# DRIVER_A.net
KiCad netlist of a schematic drawn in Altium Designer
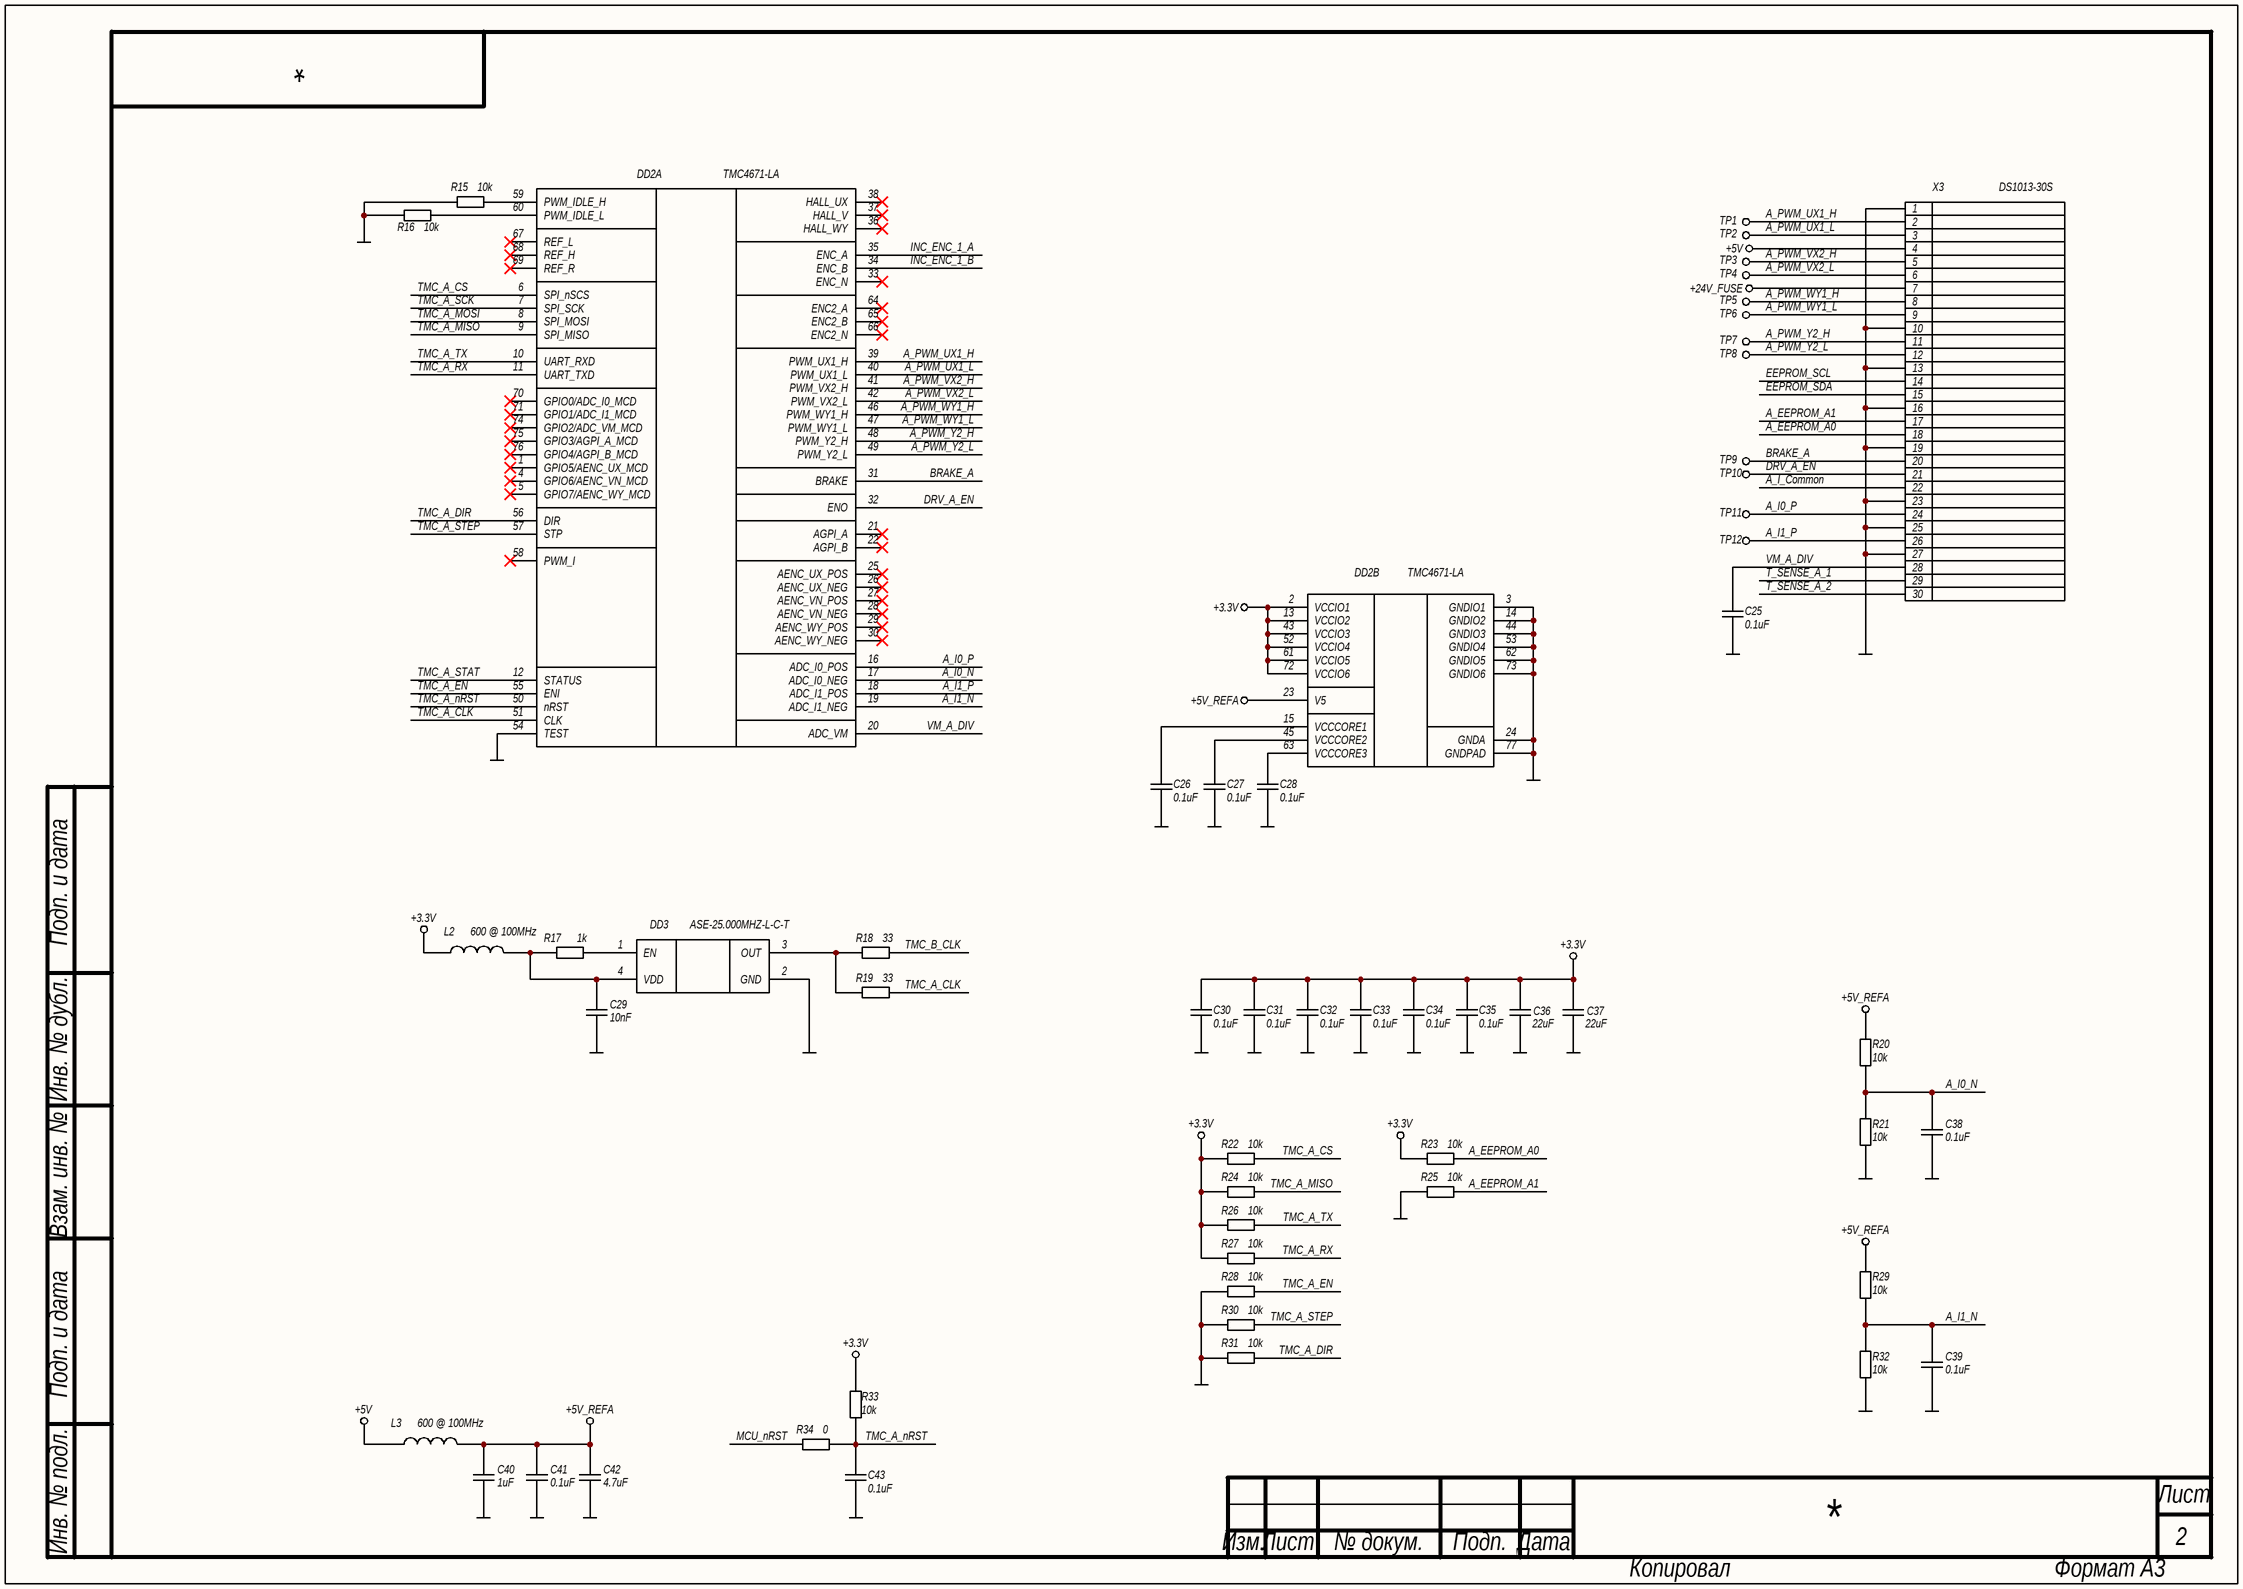
[diagram p0: DRIVER_A.SchDoc]

(export (version "E")
  (design (tool "Eeschema 10.0.6"))
  (components
    (comp (ref "C25")
      (value "0.1uF")
      (footprint "C0603N")
      (description "Конденсатор")
      (libsource (lib "Components Library") (part "CAP_FIXED"))
    )
    (comp (ref "C26")
      (value "0.1uF")
      (footprint "C0603N")
      (description "Конденсатор")
      (libsource (lib "Components Library") (part "CAP_FIXED"))
    )
    (comp (ref "C27")
      (value "0.1uF")
      (footprint "C0603N")
      (description "Конденсатор")
      (libsource (lib "Components Library") (part "CAP_FIXED"))
    )
    (comp (ref "C28")
      (value "0.1uF")
      (footprint "C0603N")
      (description "Конденсатор")
      (libsource (lib "Components Library") (part "CAP_FIXED"))
    )
    (comp (ref "C29")
      (value "10nF")
      (footprint "C0603N")
      (description "Конденсатор")
      (libsource (lib "Components Library") (part "CAP_FIXED"))
    )
    (comp (ref "C30")
      (value "0.1uF")
      (footprint "C0603N")
      (description "Конденсатор")
      (libsource (lib "Components Library") (part "CAP_FIXED"))
    )
    (comp (ref "C31")
      (value "0.1uF")
      (footprint "C0603N")
      (description "Конденсатор")
      (libsource (lib "Components Library") (part "CAP_FIXED"))
    )
    (comp (ref "C32")
      (value "0.1uF")
      (footprint "C0603N")
      (description "Конденсатор")
      (libsource (lib "Components Library") (part "CAP_FIXED"))
    )
    (comp (ref "C33")
      (value "0.1uF")
      (footprint "C0603N")
      (description "Конденсатор")
      (libsource (lib "Components Library") (part "CAP_FIXED"))
    )
    (comp (ref "C34")
      (value "0.1uF")
      (footprint "C0603N")
      (description "Конденсатор")
      (libsource (lib "Components Library") (part "CAP_FIXED"))
    )
    (comp (ref "C35")
      (value "0.1uF")
      (footprint "C0603N")
      (description "Конденсатор")
      (libsource (lib "Components Library") (part "CAP_FIXED"))
    )
    (comp (ref "C36")
      (value "22uF")
      (footprint "C0805N")
      (description "Конденсатор")
      (libsource (lib "Components Library") (part "CAP_FIXED"))
    )
    (comp (ref "C37")
      (value "22uF")
      (footprint "C0805N")
      (description "Конденсатор")
      (libsource (lib "Components Library") (part "CAP_FIXED"))
    )
    (comp (ref "C38")
      (value "0.1uF")
      (footprint "C0603N")
      (description "Конденсатор")
      (libsource (lib "Components Library") (part "CAP_FIXED"))
    )
    (comp (ref "C39")
      (value "0.1uF")
      (footprint "C0603N")
      (description "Конденсатор")
      (libsource (lib "Components Library") (part "CAP_FIXED"))
    )
    (comp (ref "C40")
      (value "1uF")
      (footprint "C0603N")
      (description "Конденсатор")
      (libsource (lib "Components Library") (part "CAP_FIXED"))
    )
    (comp (ref "C41")
      (value "0.1uF")
      (footprint "C0603N")
      (description "Конденсатор")
      (libsource (lib "Components Library") (part "CAP_FIXED"))
    )
    (comp (ref "C42")
      (value "4.7uF")
      (footprint "C0603N")
      (description "Конденсатор")
      (libsource (lib "Components Library") (part "CAP_FIXED"))
    )
    (comp (ref "C43")
      (value "0.1uF")
      (footprint "C0603N")
      (description "Конденсатор")
      (libsource (lib "Components Library") (part "CAP_FIXED"))
    )
    (comp (ref "DD2")
      (value "TMC4671-LA")
      (footprint "QFN76-EP")
      (description "Микросхема драйвер двигателя")
      (libsource (lib "Components Library") (part "TMC4671-LA"))
    )
    (comp (ref "DD3")
      (value "ASE-25.000MHZ-L-C-T")
      (footprint "ASE")
      (description "Кварцевый генератор")
      (libsource (lib "Components Library") (part "XTAL_OSC"))
    )
    (comp (ref "L2")
      (value "600 @ 100MHz")
      (footprint "FB0603N")
      (description "Фильтр ЭМП индуктивный")
      (libsource (lib "") (part "IND_FILTER_1"))
    )
    (comp (ref "L3")
      (value "600 @ 100MHz")
      (footprint "FB0603N")
      (description "Фильтр ЭМП индуктивный")
      (libsource (lib "Components Library") (part "IND_FILTER"))
    )
    (comp (ref "R15")
      (value "10k")
      (footprint "R0603N")
      (description "Резистор")
      (libsource (lib "") (part "RES_FIXED_1"))
    )
    (comp (ref "R16")
      (value "10k")
      (footprint "R0603N")
      (description "Резистор")
      (libsource (lib "") (part "RES_FIXED_1"))
    )
    (comp (ref "R17")
      (value "1k")
      (footprint "R0603N")
      (description "Резистор")
      (libsource (lib "") (part "RES_FIXED_2"))
    )
    (comp (ref "R18")
      (value "33")
      (footprint "R0603N")
      (description "Резистор")
      (libsource (lib "") (part "RES_FIXED_1"))
    )
    (comp (ref "R19")
      (value "33")
      (footprint "R0603N")
      (description "Резистор")
      (libsource (lib "") (part "RES_FIXED_1"))
    )
    (comp (ref "R20")
      (value "10k")
      (footprint "R0603N")
      (description "Резистор")
      (libsource (lib "Components Library") (part "RES_FIXED"))
    )
    (comp (ref "R21")
      (value "10k")
      (footprint "R0603N")
      (description "Резистор")
      (libsource (lib "Components Library") (part "RES_FIXED"))
    )
    (comp (ref "R22")
      (value "10k")
      (footprint "R0603N")
      (description "Резистор")
      (libsource (lib "") (part "RES_FIXED_1"))
    )
    (comp (ref "R23")
      (value "10k")
      (footprint "R0603N")
      (description "Резистор")
      (libsource (lib "") (part "RES_FIXED_1"))
    )
    (comp (ref "R24")
      (value "10k")
      (footprint "R0603N")
      (description "Резистор")
      (libsource (lib "") (part "RES_FIXED_1"))
    )
    (comp (ref "R25")
      (value "10k")
      (footprint "R0603N")
      (description "Резистор")
      (libsource (lib "") (part "RES_FIXED_1"))
    )
    (comp (ref "R26")
      (value "10k")
      (footprint "R0603N")
      (description "Резистор")
      (libsource (lib "") (part "RES_FIXED_1"))
    )
    (comp (ref "R27")
      (value "10k")
      (footprint "R0603N")
      (description "Резистор")
      (libsource (lib "") (part "RES_FIXED_1"))
    )
    (comp (ref "R28")
      (value "10k")
      (footprint "R0603N")
      (description "Резистор")
      (libsource (lib "") (part "RES_FIXED_1"))
    )
    (comp (ref "R29")
      (value "10k")
      (footprint "R0603N")
      (description "Резистор")
      (libsource (lib "Components Library") (part "RES_FIXED"))
    )
    (comp (ref "R30")
      (value "10k")
      (footprint "R0603N")
      (description "Резистор")
      (libsource (lib "") (part "RES_FIXED_1"))
    )
    (comp (ref "R31")
      (value "10k")
      (footprint "R0603N")
      (description "Резистор")
      (libsource (lib "") (part "RES_FIXED_1"))
    )
    (comp (ref "R32")
      (value "10k")
      (footprint "R0603N")
      (description "Резистор")
      (libsource (lib "Components Library") (part "RES_FIXED"))
    )
    (comp (ref "R33")
      (value "10k")
      (footprint "R0603N")
      (description "Резистор")
      (libsource (lib "Components Library") (part "RES_FIXED"))
    )
    (comp (ref "R34")
      (value "0")
      (footprint "R0603N")
      (description "Резистор")
      (libsource (lib "") (part "RES_FIXED_1"))
    )
    (comp (ref "TP1")
      (value "TEST_POINT")
      (footprint "TP_RPAD_0.8MM")
      (description "Контрольная точка")
      (libsource (lib "Components Library") (part "TEST_POINT"))
    )
    (comp (ref "TP2")
      (value "TEST_POINT")
      (footprint "TP_RPAD_0.8MM")
      (description "Контрольная точка")
      (libsource (lib "Components Library") (part "TEST_POINT"))
    )
    (comp (ref "TP3")
      (value "TEST_POINT")
      (footprint "TP_RPAD_0.8MM")
      (description "Контрольная точка")
      (libsource (lib "Components Library") (part "TEST_POINT"))
    )
    (comp (ref "TP4")
      (value "TEST_POINT")
      (footprint "TP_RPAD_0.8MM")
      (description "Контрольная точка")
      (libsource (lib "Components Library") (part "TEST_POINT"))
    )
    (comp (ref "TP5")
      (value "TEST_POINT")
      (footprint "TP_RPAD_0.8MM")
      (description "Контрольная точка")
      (libsource (lib "Components Library") (part "TEST_POINT"))
    )
    (comp (ref "TP6")
      (value "TEST_POINT")
      (footprint "TP_RPAD_0.8MM")
      (description "Контрольная точка")
      (libsource (lib "Components Library") (part "TEST_POINT"))
    )
    (comp (ref "TP7")
      (value "TEST_POINT")
      (footprint "TP_RPAD_0.8MM")
      (description "Контрольная точка")
      (libsource (lib "Components Library") (part "TEST_POINT"))
    )
    (comp (ref "TP8")
      (value "TEST_POINT")
      (footprint "TP_RPAD_0.8MM")
      (description "Контрольная точка")
      (libsource (lib "Components Library") (part "TEST_POINT"))
    )
    (comp (ref "TP9")
      (value "TEST_POINT")
      (footprint "TP_RPAD_0.8MM")
      (description "Контрольная точка")
      (libsource (lib "Components Library") (part "TEST_POINT"))
    )
    (comp (ref "TP10")
      (value "TEST_POINT")
      (footprint "TP_RPAD_0.8MM")
      (description "Контрольная точка")
      (libsource (lib "Components Library") (part "TEST_POINT"))
    )
    (comp (ref "TP11")
      (value "TEST_POINT")
      (footprint "TP_RPAD_0.8MM")
      (description "Контрольная точка")
      (libsource (lib "Components Library") (part "TEST_POINT"))
    )
    (comp (ref "TP12")
      (value "TEST_POINT")
      (footprint "TP_RPAD_0.8MM")
      (description "Контрольная точка")
      (libsource (lib "Components Library") (part "TEST_POINT"))
    )
    (comp (ref "X3")
      (value "DS1013-30S")
      (footprint "2.54_2X15_HEADER_BOX")
      (description "Разъем, 30 контактов")
      (libsource (lib "Components Library") (part "Connector 30"))
    )
  )
  (nets
    (net (code "1") (name "+3.3V") (class "Default")
      (node (ref "C30") (pin "2") (pinfunction "2_2") (pintype "passive"))
      (node (ref "C31") (pin "2") (pinfunction "2_2") (pintype "passive"))
      (node (ref "C32") (pin "2") (pinfunction "2_2") (pintype "passive"))
      (node (ref "C33") (pin "2") (pinfunction "2_2") (pintype "passive"))
      (node (ref "C34") (pin "2") (pinfunction "2_2") (pintype "passive"))
      (node (ref "C35") (pin "2") (pinfunction "2_2") (pintype "passive"))
      (node (ref "C36") (pin "2") (pinfunction "2_2") (pintype "passive"))
      (node (ref "C37") (pin "2") (pinfunction "2_2") (pintype "passive"))
      (node (ref "DD2") (pin "13") (pinfunction "VCCIO2_13") (pintype "power_in"))
      (node (ref "DD2") (pin "2") (pinfunction "VCCIO1_2") (pintype "power_in"))
      (node (ref "DD2") (pin "43") (pinfunction "VCCIO3_43") (pintype "power_in"))
      (node (ref "DD2") (pin "52") (pinfunction "VCCIO4_52") (pintype "power_in"))
      (node (ref "DD2") (pin "61") (pinfunction "VCCIO5_61") (pintype "power_in"))
      (node (ref "DD2") (pin "72") (pinfunction "VCCIO6_72") (pintype "power_in"))
      (node (ref "L2") (pin "2") (pinfunction "2_2") (pintype "passive"))
      (node (ref "R22") (pin "2") (pinfunction "2_2") (pintype "passive"))
      (node (ref "R23") (pin "2") (pinfunction "2_2") (pintype "passive"))
      (node (ref "R24") (pin "2") (pinfunction "2_2") (pintype "passive"))
      (node (ref "R26") (pin "2") (pinfunction "2_2") (pintype "passive"))
      (node (ref "R27") (pin "2") (pinfunction "2_2") (pintype "passive"))
      (node (ref "R33") (pin "2") (pinfunction "2_2") (pintype "passive"))
    )
    (net (code "2") (name "+5V") (class "Default")
      (node (ref "L3") (pin "1") (pinfunction "1_1") (pintype "passive"))
      (node (ref "X3") (pin "4") (pinfunction "4_4") (pintype "power_in"))
    )
    (net (code "3") (name "+5V_REFA") (class "Default")
      (node (ref "C40") (pin "2") (pinfunction "2_2") (pintype "passive"))
      (node (ref "C41") (pin "2") (pinfunction "2_2") (pintype "passive"))
      (node (ref "C42") (pin "2") (pinfunction "2_2") (pintype "passive"))
      (node (ref "DD2") (pin "23") (pinfunction "V5_23") (pintype "power_in"))
      (node (ref "L3") (pin "2") (pinfunction "2_2") (pintype "passive"))
      (node (ref "R20") (pin "2") (pinfunction "2_2") (pintype "passive"))
      (node (ref "R29") (pin "2") (pinfunction "2_2") (pintype "passive"))
    )
    (net (code "4") (name "+24V_FUSE") (class "Default")
      (node (ref "X3") (pin "7") (pinfunction "7_7") (pintype "power_in"))
    )
    (net (code "5") (name "/A_EEPROM_A0") (class "Default")
      (node (ref "R23") (pin "1") (pinfunction "1_1") (pintype "passive"))
      (node (ref "X3") (pin "18") (pinfunction "18_18") (pintype "power_in"))
    )
    (net (code "6") (name "/A_EEPROM_A1") (class "Default")
      (node (ref "R25") (pin "1") (pinfunction "1_1") (pintype "passive"))
      (node (ref "X3") (pin "17") (pinfunction "17_17") (pintype "power_in"))
    )
    (net (code "7") (name "/A_I0_N") (class "Default")
      (node (ref "C38") (pin "2") (pinfunction "2_2") (pintype "passive"))
      (node (ref "DD2") (pin "17") (pinfunction "ADC_I0_NEG_17") (pintype "power_in"))
      (node (ref "R20") (pin "1") (pinfunction "1_1") (pintype "passive"))
      (node (ref "R21") (pin "2") (pinfunction "2_2") (pintype "passive"))
    )
    (net (code "8") (name "/A_I0_P") (class "Default")
      (node (ref "DD2") (pin "16") (pinfunction "ADC_I0_POS_16") (pintype "power_in"))
      (node (ref "TP11") (pin "1") (pinfunction "1_1") (pintype "passive"))
      (node (ref "X3") (pin "24") (pinfunction "24_24") (pintype "power_in"))
    )
    (net (code "9") (name "/A_I1_N") (class "Default")
      (node (ref "C39") (pin "2") (pinfunction "2_2") (pintype "passive"))
      (node (ref "DD2") (pin "19") (pinfunction "ADC_I1_NEG_19") (pintype "power_in"))
      (node (ref "R29") (pin "1") (pinfunction "1_1") (pintype "passive"))
      (node (ref "R32") (pin "2") (pinfunction "2_2") (pintype "passive"))
    )
    (net (code "10") (name "/A_I1_P") (class "Default")
      (node (ref "DD2") (pin "18") (pinfunction "ADC_I1_POS_18") (pintype "power_in"))
      (node (ref "TP12") (pin "1") (pinfunction "1_1") (pintype "passive"))
      (node (ref "X3") (pin "26") (pinfunction "26_26") (pintype "power_in"))
    )
    (net (code "11") (name "/A_I_Common") (class "Default")
      (node (ref "X3") (pin "22") (pinfunction "22_22") (pintype "power_in"))
    )
    (net (code "12") (name "/A_PWM_UX1_H") (class "Default")
      (node (ref "DD2") (pin "39") (pinfunction "PWM_UX1_H_39") (pintype "power_in"))
      (node (ref "TP1") (pin "1") (pinfunction "1_1") (pintype "passive"))
      (node (ref "X3") (pin "2") (pinfunction "2_2") (pintype "power_in"))
    )
    (net (code "13") (name "/A_PWM_UX1_L") (class "Default")
      (node (ref "DD2") (pin "40") (pinfunction "PWM_UX1_L_40") (pintype "power_in"))
      (node (ref "TP2") (pin "1") (pinfunction "1_1") (pintype "passive"))
      (node (ref "X3") (pin "3") (pinfunction "3_3") (pintype "power_in"))
    )
    (net (code "14") (name "/A_PWM_VX2_H") (class "Default")
      (node (ref "DD2") (pin "41") (pinfunction "PWM_VX2_H_41") (pintype "power_in"))
      (node (ref "TP3") (pin "1") (pinfunction "1_1") (pintype "passive"))
      (node (ref "X3") (pin "5") (pinfunction "5_5") (pintype "power_in"))
    )
    (net (code "15") (name "/A_PWM_VX2_L") (class "Default")
      (node (ref "DD2") (pin "42") (pinfunction "PWM_VX2_L_42") (pintype "power_in"))
      (node (ref "TP4") (pin "1") (pinfunction "1_1") (pintype "passive"))
      (node (ref "X3") (pin "6") (pinfunction "6_6") (pintype "power_in"))
    )
    (net (code "16") (name "/A_PWM_WY1_H") (class "Default")
      (node (ref "DD2") (pin "46") (pinfunction "PWM_WY1_H_46") (pintype "power_in"))
      (node (ref "TP5") (pin "1") (pinfunction "1_1") (pintype "passive"))
      (node (ref "X3") (pin "8") (pinfunction "8_8") (pintype "power_in"))
    )
    (net (code "17") (name "/A_PWM_WY1_L") (class "Default")
      (node (ref "DD2") (pin "47") (pinfunction "PWM_WY1_L_47") (pintype "power_in"))
      (node (ref "TP6") (pin "1") (pinfunction "1_1") (pintype "passive"))
      (node (ref "X3") (pin "9") (pinfunction "9_9") (pintype "power_in"))
    )
    (net (code "18") (name "/A_PWM_Y2_H") (class "Default")
      (node (ref "DD2") (pin "48") (pinfunction "PWM_Y2_H_48") (pintype "power_in"))
      (node (ref "TP7") (pin "1") (pinfunction "1_1") (pintype "passive"))
      (node (ref "X3") (pin "11") (pinfunction "11_11") (pintype "power_in"))
    )
    (net (code "19") (name "/A_PWM_Y2_L") (class "Default")
      (node (ref "DD2") (pin "49") (pinfunction "PWM_Y2_L_49") (pintype "power_in"))
      (node (ref "TP8") (pin "1") (pinfunction "1_1") (pintype "passive"))
      (node (ref "X3") (pin "12") (pinfunction "12_12") (pintype "power_in"))
    )
    (net (code "20") (name "/BRAKE_A") (class "Default")
      (node (ref "DD2") (pin "31") (pinfunction "BRAKE_31") (pintype "power_in"))
      (node (ref "TP9") (pin "1") (pinfunction "1_1") (pintype "passive"))
      (node (ref "X3") (pin "20") (pinfunction "20_20") (pintype "power_in"))
    )
    (net (code "21") (name "/DRV_A_EN") (class "Default")
      (node (ref "DD2") (pin "32") (pinfunction "ENO_32") (pintype "power_in"))
      (node (ref "TP10") (pin "1") (pinfunction "1_1") (pintype "passive"))
      (node (ref "X3") (pin "21") (pinfunction "21_21") (pintype "power_in"))
    )
    (net (code "22") (name "/EEPROM_SCL") (class "Default")
      (node (ref "X3") (pin "14") (pinfunction "14_14") (pintype "power_in"))
    )
    (net (code "23") (name "/EEPROM_SDA") (class "Default")
      (node (ref "X3") (pin "15") (pinfunction "15_15") (pintype "power_in"))
    )
    (net (code "24") (name "/INC_ENC_1_A") (class "Default")
      (node (ref "DD2") (pin "35") (pinfunction "ENC_A_35") (pintype "power_in"))
    )
    (net (code "25") (name "/INC_ENC_1_B") (class "Default")
      (node (ref "DD2") (pin "34") (pinfunction "ENC_B_34") (pintype "power_in"))
    )
    (net (code "26") (name "/MCU_nRST") (class "Default")
      (node (ref "R34") (pin "2") (pinfunction "2_2") (pintype "passive"))
    )
    (net (code "27") (name "/TMC_A_CLK") (class "Default")
      (node (ref "DD2") (pin "51") (pinfunction "CLK_51") (pintype "power_in"))
      (node (ref "R19") (pin "1") (pinfunction "1_1") (pintype "passive"))
    )
    (net (code "28") (name "/TMC_A_CS") (class "Default")
      (node (ref "DD2") (pin "6") (pinfunction "SPI_nSCS_6") (pintype "power_in"))
      (node (ref "R22") (pin "1") (pinfunction "1_1") (pintype "passive"))
    )
    (net (code "29") (name "/TMC_A_DIR") (class "Default")
      (node (ref "DD2") (pin "56") (pinfunction "DIR_56") (pintype "power_in"))
      (node (ref "R31") (pin "1") (pinfunction "1_1") (pintype "passive"))
    )
    (net (code "30") (name "/TMC_A_EN") (class "Default")
      (node (ref "DD2") (pin "55") (pinfunction "ENI_55") (pintype "power_in"))
      (node (ref "R28") (pin "1") (pinfunction "1_1") (pintype "passive"))
    )
    (net (code "31") (name "/TMC_A_MISO") (class "Default")
      (node (ref "DD2") (pin "9") (pinfunction "SPI_MISO_9") (pintype "power_in"))
      (node (ref "R24") (pin "1") (pinfunction "1_1") (pintype "passive"))
    )
    (net (code "32") (name "/TMC_A_MOSI") (class "Default")
      (node (ref "DD2") (pin "8") (pinfunction "SPI_MOSI_8") (pintype "power_in"))
    )
    (net (code "33") (name "/TMC_A_RX") (class "Default")
      (node (ref "DD2") (pin "11") (pinfunction "UART_TXD_11") (pintype "power_in"))
      (node (ref "R27") (pin "1") (pinfunction "1_1") (pintype "passive"))
    )
    (net (code "34") (name "/TMC_A_SCK") (class "Default")
      (node (ref "DD2") (pin "7") (pinfunction "SPI_SCK_7") (pintype "power_in"))
    )
    (net (code "35") (name "/TMC_A_STAT") (class "Default")
      (node (ref "DD2") (pin "12") (pinfunction "STATUS_12") (pintype "power_in"))
    )
    (net (code "36") (name "/TMC_A_STEP") (class "Default")
      (node (ref "DD2") (pin "57") (pinfunction "STP_57") (pintype "power_in"))
      (node (ref "R30") (pin "1") (pinfunction "1_1") (pintype "passive"))
    )
    (net (code "37") (name "/TMC_A_TX") (class "Default")
      (node (ref "DD2") (pin "10") (pinfunction "UART_RXD_10") (pintype "power_in"))
      (node (ref "R26") (pin "1") (pinfunction "1_1") (pintype "passive"))
    )
    (net (code "38") (name "/TMC_A_nRST") (class "Default")
      (node (ref "C43") (pin "2") (pinfunction "2_2") (pintype "passive"))
      (node (ref "DD2") (pin "50") (pinfunction "nRST_50") (pintype "power_in"))
      (node (ref "R33") (pin "1") (pinfunction "1_1") (pintype "passive"))
      (node (ref "R34") (pin "1") (pinfunction "1_1") (pintype "passive"))
    )
    (net (code "39") (name "/TMC_B_CLK") (class "Default")
      (node (ref "R18") (pin "1") (pinfunction "1_1") (pintype "passive"))
    )
    (net (code "40") (name "/T_SENSE_A_1") (class "Default")
      (node (ref "X3") (pin "29") (pinfunction "29_29") (pintype "power_in"))
    )
    (net (code "41") (name "/T_SENSE_A_2") (class "Default")
      (node (ref "X3") (pin "30") (pinfunction "30_30") (pintype "power_in"))
    )
    (net (code "42") (name "/VM_A_DIV") (class "Default")
      (node (ref "C25") (pin "2") (pinfunction "2_2") (pintype "passive"))
      (node (ref "DD2") (pin "20") (pinfunction "ADC_VM_20") (pintype "power_in"))
      (node (ref "X3") (pin "28") (pinfunction "28_28") (pintype "power_in"))
    )
    (net (code "43") (name "GND") (class "Default")
      (node (ref "C25") (pin "1") (pinfunction "1_1") (pintype "passive"))
      (node (ref "C26") (pin "1") (pinfunction "1_1") (pintype "passive"))
      (node (ref "C27") (pin "1") (pinfunction "1_1") (pintype "passive"))
      (node (ref "C28") (pin "1") (pinfunction "1_1") (pintype "passive"))
      (node (ref "C29") (pin "2") (pinfunction "2_2") (pintype "passive"))
      (node (ref "C30") (pin "1") (pinfunction "1_1") (pintype "passive"))
      (node (ref "C31") (pin "1") (pinfunction "1_1") (pintype "passive"))
      (node (ref "C32") (pin "1") (pinfunction "1_1") (pintype "passive"))
      (node (ref "C33") (pin "1") (pinfunction "1_1") (pintype "passive"))
      (node (ref "C34") (pin "1") (pinfunction "1_1") (pintype "passive"))
      (node (ref "C35") (pin "1") (pinfunction "1_1") (pintype "passive"))
      (node (ref "C36") (pin "1") (pinfunction "1_1") (pintype "passive"))
      (node (ref "C37") (pin "1") (pinfunction "1_1") (pintype "passive"))
      (node (ref "C38") (pin "1") (pinfunction "1_1") (pintype "passive"))
      (node (ref "C39") (pin "1") (pinfunction "1_1") (pintype "passive"))
      (node (ref "C40") (pin "1") (pinfunction "1_1") (pintype "passive"))
      (node (ref "C41") (pin "1") (pinfunction "1_1") (pintype "passive"))
      (node (ref "C42") (pin "1") (pinfunction "1_1") (pintype "passive"))
      (node (ref "C43") (pin "1") (pinfunction "1_1") (pintype "passive"))
      (node (ref "DD2") (pin "14") (pinfunction "GNDIO2_14") (pintype "power_in"))
      (node (ref "DD2") (pin "24") (pinfunction "GNDA_24") (pintype "power_in"))
      (node (ref "DD2") (pin "3") (pinfunction "GNDIO1_3") (pintype "power_in"))
      (node (ref "DD2") (pin "44") (pinfunction "GNDIO3_44") (pintype "power_in"))
      (node (ref "DD2") (pin "53") (pinfunction "GNDIO4_53") (pintype "power_in"))
      (node (ref "DD2") (pin "54") (pinfunction "TEST_54") (pintype "power_in"))
      (node (ref "DD2") (pin "62") (pinfunction "GNDIO5_62") (pintype "power_in"))
      (node (ref "DD2") (pin "73") (pinfunction "GNDIO6_73") (pintype "power_in"))
      (node (ref "DD2") (pin "77") (pinfunction "GNDPAD_77") (pintype "power_in"))
      (node (ref "DD3") (pin "2") (pinfunction "GND_2") (pintype "power_in"))
      (node (ref "R15") (pin "2") (pinfunction "2_2") (pintype "passive"))
      (node (ref "R16") (pin "2") (pinfunction "2_2") (pintype "passive"))
      (node (ref "R21") (pin "1") (pinfunction "1_1") (pintype "passive"))
      (node (ref "R25") (pin "2") (pinfunction "2_2") (pintype "passive"))
      (node (ref "R28") (pin "2") (pinfunction "2_2") (pintype "passive"))
      (node (ref "R30") (pin "2") (pinfunction "2_2") (pintype "passive"))
      (node (ref "R31") (pin "2") (pinfunction "2_2") (pintype "passive"))
      (node (ref "R32") (pin "1") (pinfunction "1_1") (pintype "passive"))
      (node (ref "X3") (pin "1") (pinfunction "1_1") (pintype "power_in"))
      (node (ref "X3") (pin "10") (pinfunction "10_10") (pintype "power_in"))
      (node (ref "X3") (pin "13") (pinfunction "13_13") (pintype "power_in"))
      (node (ref "X3") (pin "16") (pinfunction "16_16") (pintype "power_in"))
      (node (ref "X3") (pin "19") (pinfunction "19_19") (pintype "power_in"))
      (node (ref "X3") (pin "23") (pinfunction "23_23") (pintype "power_in"))
      (node (ref "X3") (pin "25") (pinfunction "25_25") (pintype "power_in"))
      (node (ref "X3") (pin "27") (pinfunction "27_27") (pintype "power_in"))
    )
    (net (code "44") (name "Net-(DD2A-PWM_IDLE_H)") (class "Default")
      (node (ref "DD2") (pin "59") (pinfunction "PWM_IDLE_H_59") (pintype "power_in"))
      (node (ref "R15") (pin "1") (pinfunction "1_1") (pintype "passive"))
    )
    (net (code "45") (name "Net-(DD2A-PWM_IDLE_L)") (class "Default")
      (node (ref "DD2") (pin "60") (pinfunction "PWM_IDLE_L_60") (pintype "power_in"))
      (node (ref "R16") (pin "1") (pinfunction "1_1") (pintype "passive"))
    )
    (net (code "46") (name "Net-(DD2B-VCCCORE1)") (class "Default")
      (node (ref "C26") (pin "2") (pinfunction "2_2") (pintype "passive"))
      (node (ref "DD2") (pin "15") (pinfunction "VCCCORE1_15") (pintype "power_in"))
    )
    (net (code "47") (name "Net-(DD2B-VCCCORE2)") (class "Default")
      (node (ref "C27") (pin "2") (pinfunction "2_2") (pintype "passive"))
      (node (ref "DD2") (pin "45") (pinfunction "VCCCORE2_45") (pintype "power_in"))
    )
    (net (code "48") (name "Net-(DD2B-VCCCORE3)") (class "Default")
      (node (ref "C28") (pin "2") (pinfunction "2_2") (pintype "passive"))
      (node (ref "DD2") (pin "63") (pinfunction "VCCCORE3_63") (pintype "power_in"))
    )
    (net (code "49") (name "Net-(DD3-EN)") (class "Default")
      (node (ref "DD3") (pin "1") (pinfunction "EN_1") (pintype "power_in"))
      (node (ref "R17") (pin "2") (pinfunction "2_2") (pintype "passive"))
    )
    (net (code "50") (name "Net-(DD3-OUT)") (class "Default")
      (node (ref "DD3") (pin "3") (pinfunction "OUT_3") (pintype "power_in"))
      (node (ref "R18") (pin "2") (pinfunction "2_2") (pintype "passive"))
      (node (ref "R19") (pin "2") (pinfunction "2_2") (pintype "passive"))
    )
    (net (code "51") (name "Net-(DD3-VDD)") (class "Default")
      (node (ref "C29") (pin "1") (pinfunction "1_1") (pintype "passive"))
      (node (ref "DD3") (pin "4") (pinfunction "VDD_4") (pintype "power_in"))
      (node (ref "L2") (pin "1") (pinfunction "1_1") (pintype "passive"))
      (node (ref "R17") (pin "1") (pinfunction "1_1") (pintype "passive"))
    )
    (net (code "52") (name "unconnected-(DD2A-AENC_UX_NEG-Pad26)") (class "Default")
      (node (ref "DD2") (pin "26") (pinfunction "AENC_UX_NEG_26") (pintype "power_in+no_connect"))
    )
    (net (code "53") (name "unconnected-(DD2A-AENC_UX_POS-Pad25)") (class "Default")
      (node (ref "DD2") (pin "25") (pinfunction "AENC_UX_POS_25") (pintype "power_in+no_connect"))
    )
    (net (code "54") (name "unconnected-(DD2A-AENC_VN_NEG-Pad28)") (class "Default")
      (node (ref "DD2") (pin "28") (pinfunction "AENC_VN_NEG_28") (pintype "power_in+no_connect"))
    )
    (net (code "55") (name "unconnected-(DD2A-AENC_VN_POS-Pad27)") (class "Default")
      (node (ref "DD2") (pin "27") (pinfunction "AENC_VN_POS_27") (pintype "power_in+no_connect"))
    )
    (net (code "56") (name "unconnected-(DD2A-AENC_WY_NEG-Pad30)") (class "Default")
      (node (ref "DD2") (pin "30") (pinfunction "AENC_WY_NEG_30") (pintype "power_in+no_connect"))
    )
    (net (code "57") (name "unconnected-(DD2A-AENC_WY_POS-Pad29)") (class "Default")
      (node (ref "DD2") (pin "29") (pinfunction "AENC_WY_POS_29") (pintype "power_in+no_connect"))
    )
    (net (code "58") (name "unconnected-(DD2A-AGPI_A-Pad21)") (class "Default")
      (node (ref "DD2") (pin "21") (pinfunction "AGPI_A_21") (pintype "power_in+no_connect"))
    )
    (net (code "59") (name "unconnected-(DD2A-AGPI_B-Pad22)") (class "Default")
      (node (ref "DD2") (pin "22") (pinfunction "AGPI_B_22") (pintype "power_in+no_connect"))
    )
    (net (code "60") (name "unconnected-(DD2A-ENC2_A-Pad64)") (class "Default")
      (node (ref "DD2") (pin "64") (pinfunction "ENC2_A_64") (pintype "power_in+no_connect"))
    )
    (net (code "61") (name "unconnected-(DD2A-ENC2_B-Pad65)") (class "Default")
      (node (ref "DD2") (pin "65") (pinfunction "ENC2_B_65") (pintype "power_in+no_connect"))
    )
    (net (code "62") (name "unconnected-(DD2A-ENC2_N-Pad66)") (class "Default")
      (node (ref "DD2") (pin "66") (pinfunction "ENC2_N_66") (pintype "power_in+no_connect"))
    )
    (net (code "63") (name "unconnected-(DD2A-ENC_N-Pad33)") (class "Default")
      (node (ref "DD2") (pin "33") (pinfunction "ENC_N_33") (pintype "power_in+no_connect"))
    )
    (net (code "64") (name "unconnected-(DD2A-GPIO0{slash}ADC_I0_MCD-Pad70)") (class "Default")
      (node (ref "DD2") (pin "70") (pinfunction "GPIO0/ADC_I0_MCD_70") (pintype "power_in+no_connect"))
    )
    (net (code "65") (name "unconnected-(DD2A-GPIO1{slash}ADC_I1_MCD-Pad71)") (class "Default")
      (node (ref "DD2") (pin "71") (pinfunction "GPIO1/ADC_I1_MCD_71") (pintype "power_in+no_connect"))
    )
    (net (code "66") (name "unconnected-(DD2A-GPIO2{slash}ADC_VM_MCD-Pad74)") (class "Default")
      (node (ref "DD2") (pin "74") (pinfunction "GPIO2/ADC_VM_MCD_74") (pintype "power_in+no_connect"))
    )
    (net (code "67") (name "unconnected-(DD2A-GPIO3{slash}AGPI_A_MCD-Pad75)") (class "Default")
      (node (ref "DD2") (pin "75") (pinfunction "GPIO3/AGPI_A_MCD_75") (pintype "power_in+no_connect"))
    )
    (net (code "68") (name "unconnected-(DD2A-GPIO4{slash}AGPI_B_MCD-Pad76)") (class "Default")
      (node (ref "DD2") (pin "76") (pinfunction "GPIO4/AGPI_B_MCD_76") (pintype "power_in+no_connect"))
    )
    (net (code "69") (name "unconnected-(DD2A-GPIO5{slash}AENC_UX_MCD-Pad1)") (class "Default")
      (node (ref "DD2") (pin "1") (pinfunction "GPIO5/AENC_UX_MCD_1") (pintype "power_in+no_connect"))
    )
    (net (code "70") (name "unconnected-(DD2A-GPIO6{slash}AENC_VN_MCD-Pad4)") (class "Default")
      (node (ref "DD2") (pin "4") (pinfunction "GPIO6/AENC_VN_MCD_4") (pintype "power_in+no_connect"))
    )
    (net (code "71") (name "unconnected-(DD2A-GPIO7{slash}AENC_WY_MCD-Pad5)") (class "Default")
      (node (ref "DD2") (pin "5") (pinfunction "GPIO7/AENC_WY_MCD_5") (pintype "power_in+no_connect"))
    )
    (net (code "72") (name "unconnected-(DD2A-HALL_UX-Pad38)") (class "Default")
      (node (ref "DD2") (pin "38") (pinfunction "HALL_UX_38") (pintype "power_in+no_connect"))
    )
    (net (code "73") (name "unconnected-(DD2A-HALL_V-Pad37)") (class "Default")
      (node (ref "DD2") (pin "37") (pinfunction "HALL_V_37") (pintype "power_in+no_connect"))
    )
    (net (code "74") (name "unconnected-(DD2A-HALL_WY-Pad36)") (class "Default")
      (node (ref "DD2") (pin "36") (pinfunction "HALL_WY_36") (pintype "power_in+no_connect"))
    )
    (net (code "75") (name "unconnected-(DD2A-PWM_I-Pad58)") (class "Default")
      (node (ref "DD2") (pin "58") (pinfunction "PWM_I_58") (pintype "power_in+no_connect"))
    )
    (net (code "76") (name "unconnected-(DD2A-REF_H-Pad68)") (class "Default")
      (node (ref "DD2") (pin "68") (pinfunction "REF_H_68") (pintype "power_in+no_connect"))
    )
    (net (code "77") (name "unconnected-(DD2A-REF_L-Pad67)") (class "Default")
      (node (ref "DD2") (pin "67") (pinfunction "REF_L_67") (pintype "power_in+no_connect"))
    )
    (net (code "78") (name "unconnected-(DD2A-REF_R-Pad69)") (class "Default")
      (node (ref "DD2") (pin "69") (pinfunction "REF_R_69") (pintype "power_in+no_connect"))
    )
  )
)
